# TouchPad.net
KiCad netlist of a schematic drawn in Altium Designer
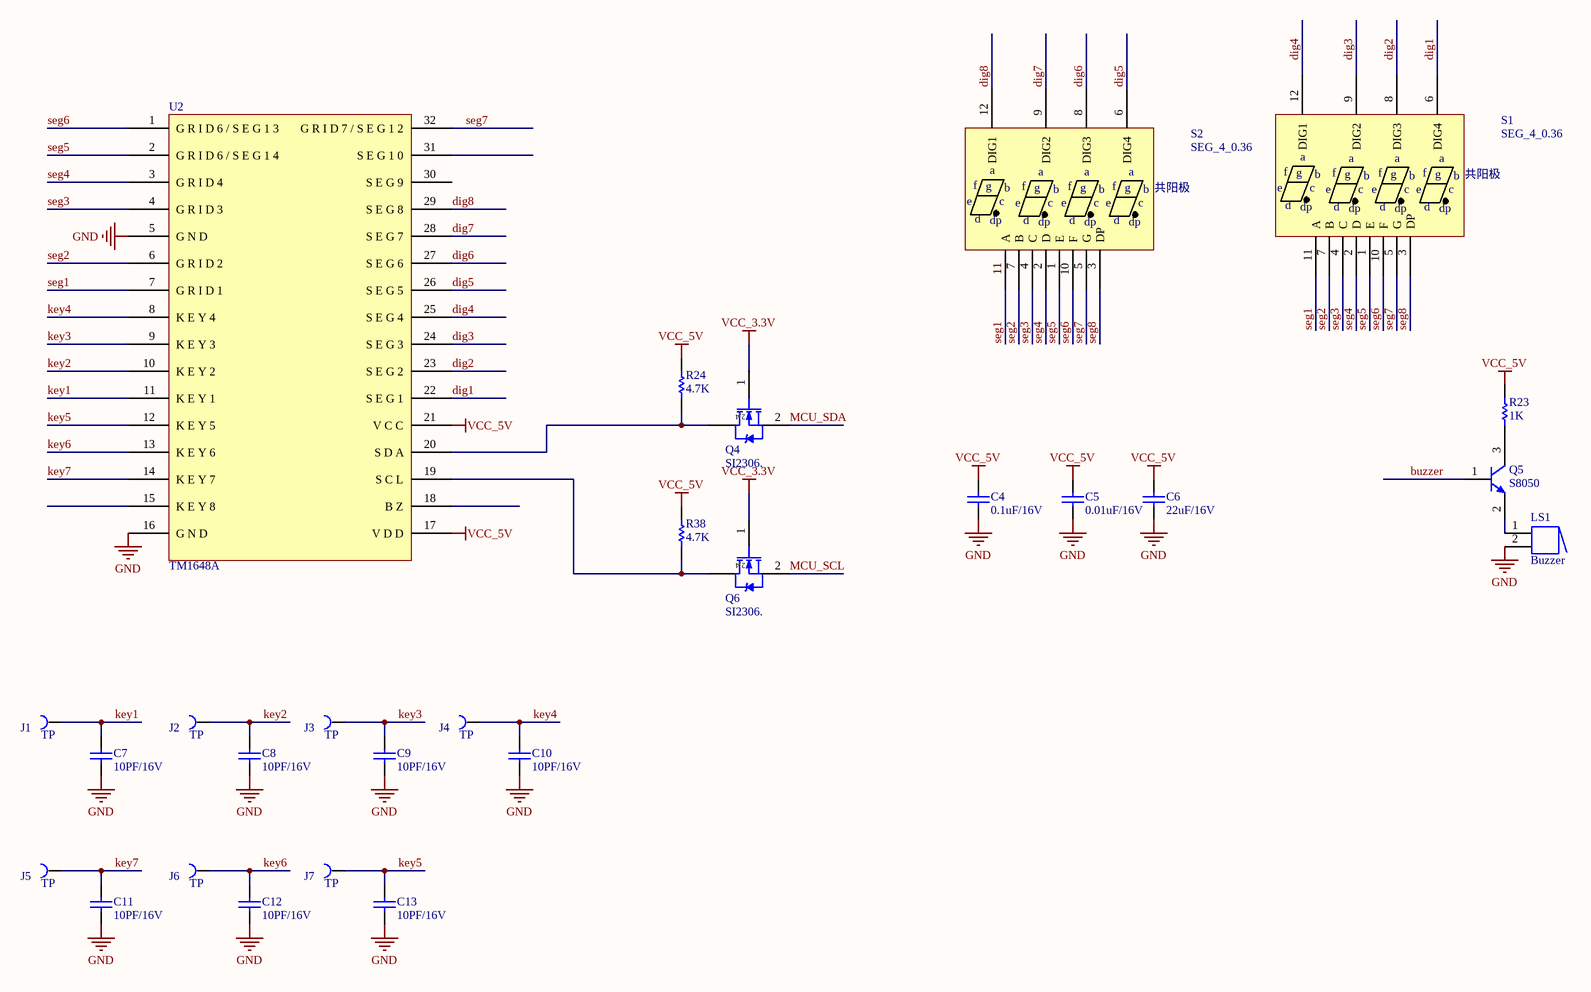
[diagram p0: TouchPad.SchDoc]

(export (version "E")
  (design (tool "Eeschema 10.0.6"))
  (components
    (comp (ref "C4")
      (value "0.1uF/16V")
      (footprint "0603C")
      (description "Capacitor")
      (fields (field (name "PUBLISHER") "Altium Limited"))
      (libsource (lib "Miscellaneous Devices") (part "Cap"))
    )
    (comp (ref "C5")
      (value "0.01uF/16V")
      (footprint "0603C")
      (description "Capacitor")
      (fields (field (name "PUBLISHER") "Altium Limited"))
      (libsource (lib "Miscellaneous Devices") (part "Cap"))
    )
    (comp (ref "C6")
      (value "22uF/16V")
      (footprint "0805C")
      (description "Capacitor")
      (fields (field (name "PUBLISHER") "Altium Limited"))
      (libsource (lib "Miscellaneous Devices") (part "Cap"))
    )
    (comp (ref "C7")
      (value "10PF/16V")
      (footprint "0603C")
      (description "Capacitor")
      (fields (field (name "PUBLISHER") "Altium Limited"))
      (libsource (lib "Miscellaneous Devices") (part "Cap"))
    )
    (comp (ref "C8")
      (value "10PF/16V")
      (footprint "0603C")
      (description "Capacitor")
      (fields (field (name "PUBLISHER") "Altium Limited"))
      (libsource (lib "Miscellaneous Devices") (part "Cap"))
    )
    (comp (ref "C9")
      (value "10PF/16V")
      (footprint "0603C")
      (description "Capacitor")
      (fields (field (name "PUBLISHER") "Altium Limited"))
      (libsource (lib "Miscellaneous Devices") (part "Cap"))
    )
    (comp (ref "C10")
      (value "10PF/16V")
      (footprint "0603C")
      (description "Capacitor")
      (fields (field (name "PUBLISHER") "Altium Limited"))
      (libsource (lib "Miscellaneous Devices") (part "Cap"))
    )
    (comp (ref "C11")
      (value "10PF/16V")
      (footprint "0603C")
      (description "Capacitor")
      (fields (field (name "PUBLISHER") "Altium Limited"))
      (libsource (lib "Miscellaneous Devices") (part "Cap"))
    )
    (comp (ref "C12")
      (value "10PF/16V")
      (footprint "0603C")
      (description "Capacitor")
      (fields (field (name "PUBLISHER") "Altium Limited"))
      (libsource (lib "Miscellaneous Devices") (part "Cap"))
    )
    (comp (ref "C13")
      (value "10PF/16V")
      (footprint "0603C")
      (description "Capacitor")
      (fields (field (name "PUBLISHER") "Altium Limited"))
      (libsource (lib "Miscellaneous Devices") (part "Cap"))
    )
    (comp (ref "J1")
      (value "TP")
      (footprint "Pcblib_20110825:TOUCHU_PAD")
      (description "TEST_3P")
      (libsource (lib "stm32") (part "TOUCH_PAD"))
    )
    (comp (ref "J2")
      (value "TP")
      (footprint "Pcblib_20110825:TOUCHU_PAD")
      (description "TEST_3P")
      (libsource (lib "stm32") (part "TOUCH_PAD"))
    )
    (comp (ref "J3")
      (value "TP")
      (footprint "Pcblib_20110825:TOUCHU_PAD")
      (description "TEST_3P")
      (libsource (lib "stm32") (part "TOUCH_PAD"))
    )
    (comp (ref "J4")
      (value "TP")
      (footprint "Pcblib_20110825:TOUCHU_PAD")
      (description "TEST_3P")
      (libsource (lib "stm32") (part "TOUCH_PAD"))
    )
    (comp (ref "J5")
      (value "TP")
      (footprint "Pcblib_20110825:TOUCHU_PAD")
      (description "TEST_3P")
      (libsource (lib "stm32") (part "TOUCH_PAD"))
    )
    (comp (ref "J6")
      (value "TP")
      (footprint "Pcblib_20110825:TOUCHU_PAD")
      (description "TEST_3P")
      (libsource (lib "stm32") (part "TOUCH_PAD"))
    )
    (comp (ref "J7")
      (value "TP")
      (footprint "Pcblib_20110825:TOUCHU_PAD")
      (description "TEST_3P")
      (libsource (lib "stm32") (part "TOUCH_PAD"))
    )
    (comp (ref "LS1")
      (value "Buzzer")
      (footprint "Pcblib_20110825:BUFFER_0905")
      (description "Magnetic Transducer Buzzer")
      (fields (field (name "PUBLISHER") "Altium Limited"))
      (libsource (lib "Miscellaneous Devices") (part "Buzzer"))
    )
    (comp (ref "Q4")
      (value "SI2306.")
      (footprint "SOT23-3")
      (description "BUK92150-55A")
      (fields (field (name "PUBLISHER") "Altium Limited"))
      (libsource (lib "Schlib1") (part "BUK92150-55A"))
    )
    (comp (ref "Q5")
      (value "S8050")
      (footprint "sot23-3")
      (description "NPN Bipolar Transistor")
      (fields (field (name "PUBLISHER") "Altium Limited"))
      (libsource (lib "Miscellaneous Devices") (part "NPN"))
    )
    (comp (ref "Q6")
      (value "SI2306.")
      (footprint "SOT23-3")
      (description "BUK92150-55A")
      (fields (field (name "PUBLISHER") "Altium Limited"))
      (libsource (lib "Schlib1") (part "BUK92150-55A"))
    )
    (comp (ref "R23")
      (value "1K")
      (footprint "0603R")
      (description "Resistor")
      (fields (field (name "PUBLISHER") "Altium Limited"))
      (libsource (lib "Miscellaneous Devices") (part "Res1"))
    )
    (comp (ref "R24")
      (value "4.7K")
      (footprint "0603R")
      (description "Resistor")
      (fields (field (name "PUBLISHER") "Altium Limited"))
      (libsource (lib "Miscellaneous Devices") (part "Res1"))
    )
    (comp (ref "R38")
      (value "4.7K")
      (footprint "0603R")
      (description "Resistor")
      (fields (field (name "PUBLISHER") "Altium Limited"))
      (libsource (lib "Miscellaneous Devices") (part "Res1"))
    )
    (comp (ref "S1")
      (value "SEG_4_0.36")
      (footprint "DISPLAY_0.36INCH_4")
      (libsource (lib "stm32") (part "SEG_4_0.36"))
    )
    (comp (ref "S2")
      (value "SEG_4_0.36")
      (footprint "DISPLAY_0.36INCH_4")
      (libsource (lib "stm32") (part "SEG_4_0.36"))
    )
    (comp (ref "U2")
      (value "TM1648A")
      (footprint "SOP127P1040X265-32N")
      (libsource (lib "stm32") (part "TM1648A"))
    )
  )
  (nets
    (net (code "1") (name "/MCU_SCL") (class "Default")
      (node (ref "Q6") (pin "2") (pinfunction "S_2") (pintype "passive"))
    )
    (net (code "2") (name "/MCU_SDA") (class "Default")
      (node (ref "Q4") (pin "2") (pinfunction "S_2") (pintype "passive"))
    )
    (net (code "3") (name "/buzzer") (class "Default")
      (node (ref "Q5") (pin "1") (pinfunction "B_1") (pintype "passive"))
    )
    (net (code "4") (name "/dig1") (class "Default")
      (node (ref "S1") (pin "6") (pinfunction "DIG4_6") (pintype "passive"))
      (node (ref "U2") (pin "22") (pinfunction "S_E_G_1_22") (pintype "passive"))
    )
    (net (code "5") (name "/dig2") (class "Default")
      (node (ref "S1") (pin "8") (pinfunction "DIG3_8") (pintype "passive"))
      (node (ref "U2") (pin "23") (pinfunction "S_E_G_2_23") (pintype "passive"))
    )
    (net (code "6") (name "/dig3") (class "Default")
      (node (ref "S1") (pin "9") (pinfunction "DIG2_9") (pintype "passive"))
      (node (ref "U2") (pin "24") (pinfunction "S_E_G_3_24") (pintype "passive"))
    )
    (net (code "7") (name "/dig4") (class "Default")
      (node (ref "S1") (pin "12") (pinfunction "DIG1_12") (pintype "passive"))
      (node (ref "U2") (pin "25") (pinfunction "S_E_G_4_25") (pintype "passive"))
    )
    (net (code "8") (name "/dig5") (class "Default")
      (node (ref "S2") (pin "6") (pinfunction "DIG4_6") (pintype "passive"))
      (node (ref "U2") (pin "26") (pinfunction "S_E_G_5_26") (pintype "passive"))
    )
    (net (code "9") (name "/dig6") (class "Default")
      (node (ref "S2") (pin "8") (pinfunction "DIG3_8") (pintype "passive"))
      (node (ref "U2") (pin "27") (pinfunction "S_E_G_6_27") (pintype "passive"))
    )
    (net (code "10") (name "/dig7") (class "Default")
      (node (ref "S2") (pin "9") (pinfunction "DIG2_9") (pintype "passive"))
      (node (ref "U2") (pin "28") (pinfunction "S_E_G_7_28") (pintype "passive"))
    )
    (net (code "11") (name "/dig8") (class "Default")
      (node (ref "S2") (pin "12") (pinfunction "DIG1_12") (pintype "passive"))
      (node (ref "U2") (pin "29") (pinfunction "S_E_G_8_29") (pintype "passive"))
    )
    (net (code "12") (name "/key1") (class "Default")
      (node (ref "C7") (pin "2") (pinfunction "2_2") (pintype "passive"))
      (node (ref "J1") (pin "1") (pinfunction "1_1") (pintype "passive"))
      (node (ref "U2") (pin "11") (pinfunction "K_E_Y_1_11") (pintype "passive"))
    )
    (net (code "13") (name "/key2") (class "Default")
      (node (ref "C8") (pin "2") (pinfunction "2_2") (pintype "passive"))
      (node (ref "J2") (pin "1") (pinfunction "1_1") (pintype "passive"))
      (node (ref "U2") (pin "10") (pinfunction "K_E_Y_2_10") (pintype "passive"))
    )
    (net (code "14") (name "/key3") (class "Default")
      (node (ref "C9") (pin "2") (pinfunction "2_2") (pintype "passive"))
      (node (ref "J3") (pin "1") (pinfunction "1_1") (pintype "passive"))
      (node (ref "U2") (pin "9") (pinfunction "K_E_Y_3_9") (pintype "passive"))
    )
    (net (code "15") (name "/key4") (class "Default")
      (node (ref "C10") (pin "2") (pinfunction "2_2") (pintype "passive"))
      (node (ref "J4") (pin "1") (pinfunction "1_1") (pintype "passive"))
      (node (ref "U2") (pin "8") (pinfunction "K_E_Y_4_8") (pintype "passive"))
    )
    (net (code "16") (name "/key5") (class "Default")
      (node (ref "C13") (pin "2") (pinfunction "2_2") (pintype "passive"))
      (node (ref "J7") (pin "1") (pinfunction "1_1") (pintype "passive"))
      (node (ref "U2") (pin "12") (pinfunction "K_E_Y_5_12") (pintype "passive"))
    )
    (net (code "17") (name "/key6") (class "Default")
      (node (ref "C12") (pin "2") (pinfunction "2_2") (pintype "passive"))
      (node (ref "J6") (pin "1") (pinfunction "1_1") (pintype "passive"))
      (node (ref "U2") (pin "13") (pinfunction "K_E_Y_6_13") (pintype "passive"))
    )
    (net (code "18") (name "/key7") (class "Default")
      (node (ref "C11") (pin "2") (pinfunction "2_2") (pintype "passive"))
      (node (ref "J5") (pin "1") (pinfunction "1_1") (pintype "passive"))
      (node (ref "U2") (pin "14") (pinfunction "K_E_Y_7_14") (pintype "passive"))
    )
    (net (code "19") (name "/seg1") (class "Default")
      (node (ref "S1") (pin "11") (pinfunction "A_11") (pintype "passive"))
      (node (ref "S2") (pin "11") (pinfunction "A_11") (pintype "passive"))
      (node (ref "U2") (pin "7") (pinfunction "G_R_I_D_1_7") (pintype "passive"))
    )
    (net (code "20") (name "/seg2") (class "Default")
      (node (ref "S1") (pin "7") (pinfunction "B_7") (pintype "passive"))
      (node (ref "S2") (pin "7") (pinfunction "B_7") (pintype "passive"))
      (node (ref "U2") (pin "6") (pinfunction "G_R_I_D_2_6") (pintype "passive"))
    )
    (net (code "21") (name "/seg3") (class "Default")
      (node (ref "S1") (pin "4") (pinfunction "C_4") (pintype "passive"))
      (node (ref "S2") (pin "4") (pinfunction "C_4") (pintype "passive"))
      (node (ref "U2") (pin "4") (pinfunction "G_R_I_D_3_4") (pintype "passive"))
    )
    (net (code "22") (name "/seg4") (class "Default")
      (node (ref "S1") (pin "2") (pinfunction "D_2") (pintype "passive"))
      (node (ref "S2") (pin "2") (pinfunction "D_2") (pintype "passive"))
      (node (ref "U2") (pin "3") (pinfunction "G_R_I_D_4_3") (pintype "passive"))
    )
    (net (code "23") (name "/seg5") (class "Default")
      (node (ref "S1") (pin "1") (pinfunction "E_1") (pintype "passive"))
      (node (ref "S2") (pin "1") (pinfunction "E_1") (pintype "passive"))
      (node (ref "U2") (pin "2") (pinfunction "G_R_I_D_6_/_S_E_G_1_4_2") (pintype "passive"))
    )
    (net (code "24") (name "/seg6") (class "Default")
      (node (ref "S1") (pin "10") (pinfunction "F_10") (pintype "passive"))
      (node (ref "S2") (pin "10") (pinfunction "F_10") (pintype "passive"))
      (node (ref "U2") (pin "1") (pinfunction "G_R_I_D_6_/_S_E_G_1_3_1") (pintype "passive"))
    )
    (net (code "25") (name "/seg7") (class "Default")
      (node (ref "S1") (pin "5") (pinfunction "G_5") (pintype "passive"))
      (node (ref "S2") (pin "5") (pinfunction "G_5") (pintype "passive"))
      (node (ref "U2") (pin "32") (pinfunction "G_R_I_D_7_/_S_E_G_1_2_32") (pintype "passive"))
    )
    (net (code "26") (name "/seg8") (class "Default")
      (node (ref "S1") (pin "3") (pinfunction "DP_3") (pintype "passive"))
      (node (ref "S2") (pin "3") (pinfunction "DP_3") (pintype "passive"))
    )
    (net (code "27") (name "GND") (class "Default")
      (node (ref "C10") (pin "1") (pinfunction "1_1") (pintype "passive"))
      (node (ref "C11") (pin "1") (pinfunction "1_1") (pintype "passive"))
      (node (ref "C12") (pin "1") (pinfunction "1_1") (pintype "passive"))
      (node (ref "C13") (pin "1") (pinfunction "1_1") (pintype "passive"))
      (node (ref "C4") (pin "2") (pinfunction "2_2") (pintype "passive"))
      (node (ref "C5") (pin "2") (pinfunction "2_2") (pintype "passive"))
      (node (ref "C6") (pin "2") (pinfunction "2_2") (pintype "passive"))
      (node (ref "C7") (pin "1") (pinfunction "1_1") (pintype "passive"))
      (node (ref "C8") (pin "1") (pinfunction "1_1") (pintype "passive"))
      (node (ref "C9") (pin "1") (pinfunction "1_1") (pintype "passive"))
      (node (ref "LS1") (pin "2") (pinfunction "2_2") (pintype "passive"))
      (node (ref "U2") (pin "16") (pinfunction "G_N_D_16") (pintype "passive"))
      (node (ref "U2") (pin "5") (pinfunction "G_N_D_5") (pintype "passive"))
    )
    (net (code "28") (name "Net-(Q4-D)") (class "Default")
      (node (ref "Q4") (pin "3") (pinfunction "D_3") (pintype "passive"))
      (node (ref "R24") (pin "1") (pinfunction "1_1") (pintype "passive"))
      (node (ref "U2") (pin "20") (pinfunction "S_D_A_20") (pintype "passive"))
    )
    (net (code "29") (name "Net-(Q5-C)") (class "Default")
      (node (ref "Q5") (pin "3") (pinfunction "C_3") (pintype "passive"))
      (node (ref "R23") (pin "2") (pinfunction "2_2") (pintype "passive"))
    )
    (net (code "30") (name "Net-(Q5-E)") (class "Default")
      (node (ref "LS1") (pin "1") (pinfunction "1_1") (pintype "passive"))
      (node (ref "Q5") (pin "2") (pinfunction "E_2") (pintype "passive"))
    )
    (net (code "31") (name "Net-(Q6-D)") (class "Default")
      (node (ref "Q6") (pin "3") (pinfunction "D_3") (pintype "passive"))
      (node (ref "R38") (pin "1") (pinfunction "1_1") (pintype "passive"))
      (node (ref "U2") (pin "19") (pinfunction "S_C_L_19") (pintype "passive"))
    )
    (net (code "32") (name "VCC_3.3V") (class "Default")
      (node (ref "Q4") (pin "1") (pinfunction "G_1") (pintype "passive"))
      (node (ref "Q6") (pin "1") (pinfunction "G_1") (pintype "passive"))
    )
    (net (code "33") (name "VCC_5V") (class "Default")
      (node (ref "C4") (pin "1") (pinfunction "1_1") (pintype "passive"))
      (node (ref "C5") (pin "1") (pinfunction "1_1") (pintype "passive"))
      (node (ref "C6") (pin "1") (pinfunction "1_1") (pintype "passive"))
      (node (ref "R23") (pin "1") (pinfunction "1_1") (pintype "passive"))
      (node (ref "R24") (pin "2") (pinfunction "2_2") (pintype "passive"))
      (node (ref "R38") (pin "2") (pinfunction "2_2") (pintype "passive"))
      (node (ref "U2") (pin "17") (pinfunction "V_D_D_17") (pintype "passive"))
      (node (ref "U2") (pin "21") (pinfunction "V_C_C_21") (pintype "passive"))
    )
    (net (code "34") (name "unconnected-(U2-B_Z-Pad18)") (class "Default")
      (node (ref "U2") (pin "18") (pinfunction "B_Z_18") (pintype "passive"))
    )
    (net (code "35") (name "unconnected-(U2-K_E_Y_8-Pad15)") (class "Default")
      (node (ref "U2") (pin "15") (pinfunction "K_E_Y_8_15") (pintype "passive"))
    )
    (net (code "36") (name "unconnected-(U2-S_E_G_1_0-Pad31)") (class "Default")
      (node (ref "U2") (pin "31") (pinfunction "S_E_G_1_0_31") (pintype "passive"))
    )
    (net (code "37") (name "unconnected-(U2-S_E_G_9-Pad30)") (class "Default")
      (node (ref "U2") (pin "30") (pinfunction "S_E_G_9_30") (pintype "passive"))
    )
  )
)
